# 2_waffling80_classyTKL-NMB_matrix.net
KiCad netlist of a schematic drawn in Altium Designer
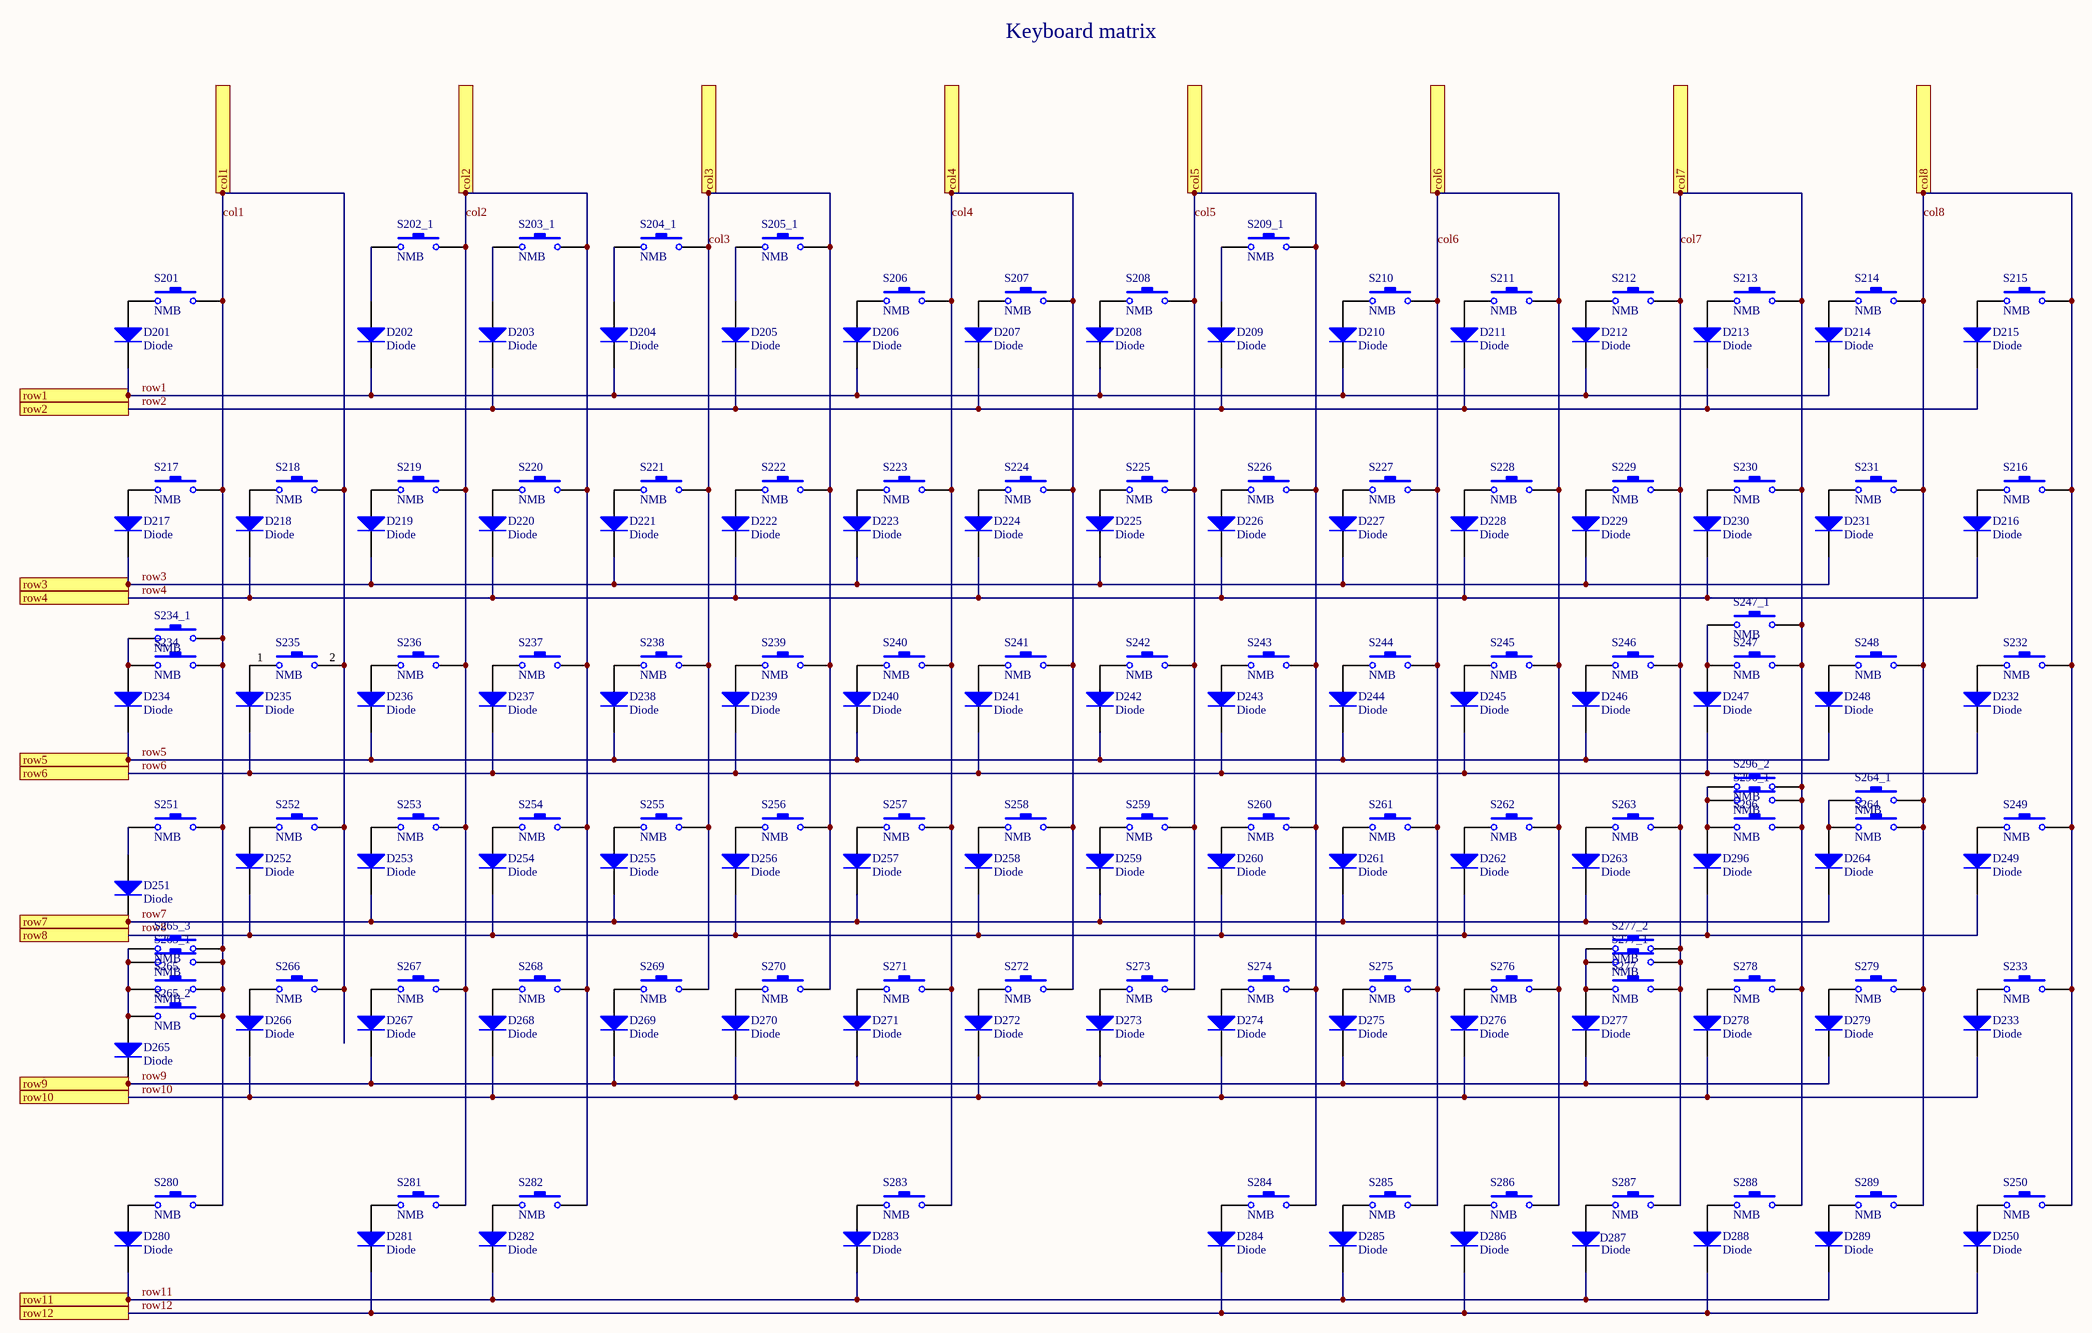
[diagram p0: 2_waffling80_classyTKL-NMB_matrix.SchDoc]

(export (version "E")
  (design (tool "Eeschema 10.0.6"))
  (components
    (comp (ref "D201")
      (value "Diode")
      (footprint "SOD-123")
      (description "Default Diode")
      (fields (field (name "LCSC PART #") "C81598") (field (name "MRF.PART") "1N4148W"))
      (libsource (lib "Miscellaneous Devices") (part "Diode"))
    )
    (comp (ref "D202")
      (value "Diode")
      (footprint "SOD-123")
      (description "Default Diode")
      (fields (field (name "LCSC PART #") "C81598") (field (name "MRF.PART") "1N4148W"))
      (libsource (lib "Miscellaneous Devices") (part "Diode"))
    )
    (comp (ref "D203")
      (value "Diode")
      (footprint "SOD-123")
      (description "Default Diode")
      (fields (field (name "LCSC PART #") "C81598") (field (name "MRF.PART") "1N4148W"))
      (libsource (lib "Miscellaneous Devices") (part "Diode"))
    )
    (comp (ref "D204")
      (value "Diode")
      (footprint "SOD-123")
      (description "Default Diode")
      (fields (field (name "LCSC PART #") "C81598") (field (name "MRF.PART") "1N4148W"))
      (libsource (lib "Miscellaneous Devices") (part "Diode"))
    )
    (comp (ref "D205")
      (value "Diode")
      (footprint "SOD-123")
      (description "Default Diode")
      (fields (field (name "LCSC PART #") "C81598") (field (name "MRF.PART") "1N4148W"))
      (libsource (lib "Miscellaneous Devices") (part "Diode"))
    )
    (comp (ref "D206")
      (value "Diode")
      (footprint "SOD-123")
      (description "Default Diode")
      (fields (field (name "LCSC PART #") "C81598") (field (name "MRF.PART") "1N4148W"))
      (libsource (lib "Miscellaneous Devices") (part "Diode"))
    )
    (comp (ref "D207")
      (value "Diode")
      (footprint "SOD-123")
      (description "Default Diode")
      (fields (field (name "LCSC PART #") "C81598") (field (name "MRF.PART") "1N4148W"))
      (libsource (lib "Miscellaneous Devices") (part "Diode"))
    )
    (comp (ref "D208")
      (value "Diode")
      (footprint "SOD-123")
      (description "Default Diode")
      (fields (field (name "LCSC PART #") "C81598") (field (name "MRF.PART") "1N4148W"))
      (libsource (lib "Miscellaneous Devices") (part "Diode"))
    )
    (comp (ref "D209")
      (value "Diode")
      (footprint "SOD-123")
      (description "Default Diode")
      (fields (field (name "LCSC PART #") "C81598") (field (name "MRF.PART") "1N4148W"))
      (libsource (lib "Miscellaneous Devices") (part "Diode"))
    )
    (comp (ref "D210")
      (value "Diode")
      (footprint "SOD-123")
      (description "Default Diode")
      (fields (field (name "LCSC PART #") "C81598") (field (name "MRF.PART") "1N4148W"))
      (libsource (lib "Miscellaneous Devices") (part "Diode"))
    )
    (comp (ref "D211")
      (value "Diode")
      (footprint "SOD-123")
      (description "Default Diode")
      (fields (field (name "LCSC PART #") "C81598") (field (name "MRF.PART") "1N4148W"))
      (libsource (lib "Miscellaneous Devices") (part "Diode"))
    )
    (comp (ref "D212")
      (value "Diode")
      (footprint "SOD-123")
      (description "Default Diode")
      (fields (field (name "LCSC PART #") "C81598") (field (name "MRF.PART") "1N4148W"))
      (libsource (lib "Miscellaneous Devices") (part "Diode"))
    )
    (comp (ref "D213")
      (value "Diode")
      (footprint "SOD-123")
      (description "Default Diode")
      (fields (field (name "LCSC PART #") "C81598") (field (name "MRF.PART") "1N4148W"))
      (libsource (lib "Miscellaneous Devices") (part "Diode"))
    )
    (comp (ref "D214")
      (value "Diode")
      (footprint "SOD-123")
      (description "Default Diode")
      (fields (field (name "LCSC PART #") "C81598") (field (name "MRF.PART") "1N4148W"))
      (libsource (lib "Miscellaneous Devices") (part "Diode"))
    )
    (comp (ref "D215")
      (value "Diode")
      (footprint "SOD-123")
      (description "Default Diode")
      (fields (field (name "LCSC PART #") "C81598") (field (name "MRF.PART") "1N4148W"))
      (libsource (lib "Miscellaneous Devices") (part "Diode"))
    )
    (comp (ref "D216")
      (value "Diode")
      (footprint "SOD-123")
      (description "Default Diode")
      (fields (field (name "LCSC PART #") "C81598") (field (name "MRF.PART") "1N4148W"))
      (libsource (lib "Miscellaneous Devices") (part "Diode"))
    )
    (comp (ref "D217")
      (value "Diode")
      (footprint "SOD-123")
      (description "Default Diode")
      (fields (field (name "LCSC PART #") "C81598") (field (name "MRF.PART") "1N4148W"))
      (libsource (lib "Miscellaneous Devices") (part "Diode"))
    )
    (comp (ref "D218")
      (value "Diode")
      (footprint "SOD-123")
      (description "Default Diode")
      (fields (field (name "LCSC PART #") "C81598") (field (name "MRF.PART") "1N4148W"))
      (libsource (lib "Miscellaneous Devices") (part "Diode"))
    )
    (comp (ref "D219")
      (value "Diode")
      (footprint "SOD-123")
      (description "Default Diode")
      (fields (field (name "LCSC PART #") "C81598") (field (name "MRF.PART") "1N4148W"))
      (libsource (lib "Miscellaneous Devices") (part "Diode"))
    )
    (comp (ref "D220")
      (value "Diode")
      (footprint "SOD-123")
      (description "Default Diode")
      (fields (field (name "LCSC PART #") "C81598") (field (name "MRF.PART") "1N4148W"))
      (libsource (lib "Miscellaneous Devices") (part "Diode"))
    )
    (comp (ref "D221")
      (value "Diode")
      (footprint "SOD-123")
      (description "Default Diode")
      (fields (field (name "LCSC PART #") "C81598") (field (name "MRF.PART") "1N4148W"))
      (libsource (lib "Miscellaneous Devices") (part "Diode"))
    )
    (comp (ref "D222")
      (value "Diode")
      (footprint "SOD-123")
      (description "Default Diode")
      (fields (field (name "LCSC PART #") "C81598") (field (name "MRF.PART") "1N4148W"))
      (libsource (lib "Miscellaneous Devices") (part "Diode"))
    )
    (comp (ref "D223")
      (value "Diode")
      (footprint "SOD-123")
      (description "Default Diode")
      (fields (field (name "LCSC PART #") "C81598") (field (name "MRF.PART") "1N4148W"))
      (libsource (lib "Miscellaneous Devices") (part "Diode"))
    )
    (comp (ref "D224")
      (value "Diode")
      (footprint "SOD-123")
      (description "Default Diode")
      (fields (field (name "LCSC PART #") "C81598") (field (name "MRF.PART") "1N4148W"))
      (libsource (lib "Miscellaneous Devices") (part "Diode"))
    )
    (comp (ref "D225")
      (value "Diode")
      (footprint "SOD-123")
      (description "Default Diode")
      (fields (field (name "LCSC PART #") "C81598") (field (name "MRF.PART") "1N4148W"))
      (libsource (lib "Miscellaneous Devices") (part "Diode"))
    )
    (comp (ref "D226")
      (value "Diode")
      (footprint "SOD-123")
      (description "Default Diode")
      (fields (field (name "LCSC PART #") "C81598") (field (name "MRF.PART") "1N4148W"))
      (libsource (lib "Miscellaneous Devices") (part "Diode"))
    )
    (comp (ref "D227")
      (value "Diode")
      (footprint "SOD-123")
      (description "Default Diode")
      (fields (field (name "LCSC PART #") "C81598") (field (name "MRF.PART") "1N4148W"))
      (libsource (lib "Miscellaneous Devices") (part "Diode"))
    )
    (comp (ref "D228")
      (value "Diode")
      (footprint "SOD-123")
      (description "Default Diode")
      (fields (field (name "LCSC PART #") "C81598") (field (name "MRF.PART") "1N4148W"))
      (libsource (lib "Miscellaneous Devices") (part "Diode"))
    )
    (comp (ref "D229")
      (value "Diode")
      (footprint "SOD-123")
      (description "Default Diode")
      (fields (field (name "LCSC PART #") "C81598") (field (name "MRF.PART") "1N4148W"))
      (libsource (lib "Miscellaneous Devices") (part "Diode"))
    )
    (comp (ref "D230")
      (value "Diode")
      (footprint "SOD-123")
      (description "Default Diode")
      (fields (field (name "LCSC PART #") "C81598") (field (name "MRF.PART") "1N4148W"))
      (libsource (lib "Miscellaneous Devices") (part "Diode"))
    )
    (comp (ref "D231")
      (value "Diode")
      (footprint "SOD-123")
      (description "Default Diode")
      (fields (field (name "LCSC PART #") "C81598") (field (name "MRF.PART") "1N4148W"))
      (libsource (lib "Miscellaneous Devices") (part "Diode"))
    )
    (comp (ref "D232")
      (value "Diode")
      (footprint "SOD-123")
      (description "Default Diode")
      (fields (field (name "LCSC PART #") "C81598") (field (name "MRF.PART") "1N4148W"))
      (libsource (lib "Miscellaneous Devices") (part "Diode"))
    )
    (comp (ref "D233")
      (value "Diode")
      (footprint "SOD-123")
      (description "Default Diode")
      (fields (field (name "LCSC PART #") "C81598") (field (name "MRF.PART") "1N4148W"))
      (libsource (lib "Miscellaneous Devices") (part "Diode"))
    )
    (comp (ref "D234")
      (value "Diode")
      (footprint "SOD-123")
      (description "Default Diode")
      (fields (field (name "LCSC PART #") "C81598") (field (name "MRF.PART") "1N4148W"))
      (libsource (lib "Miscellaneous Devices") (part "Diode"))
    )
    (comp (ref "D235")
      (value "Diode")
      (footprint "SOD-123")
      (description "Default Diode")
      (fields (field (name "LCSC PART #") "C81598") (field (name "MRF.PART") "1N4148W"))
      (libsource (lib "Miscellaneous Devices") (part "Diode"))
    )
    (comp (ref "D236")
      (value "Diode")
      (footprint "SOD-123")
      (description "Default Diode")
      (fields (field (name "LCSC PART #") "C81598") (field (name "MRF.PART") "1N4148W"))
      (libsource (lib "Miscellaneous Devices") (part "Diode"))
    )
    (comp (ref "D237")
      (value "Diode")
      (footprint "SOD-123")
      (description "Default Diode")
      (fields (field (name "LCSC PART #") "C81598") (field (name "MRF.PART") "1N4148W"))
      (libsource (lib "Miscellaneous Devices") (part "Diode"))
    )
    (comp (ref "D238")
      (value "Diode")
      (footprint "SOD-123")
      (description "Default Diode")
      (fields (field (name "LCSC PART #") "C81598") (field (name "MRF.PART") "1N4148W"))
      (libsource (lib "Miscellaneous Devices") (part "Diode"))
    )
    (comp (ref "D239")
      (value "Diode")
      (footprint "SOD-123")
      (description "Default Diode")
      (fields (field (name "LCSC PART #") "C81598") (field (name "MRF.PART") "1N4148W"))
      (libsource (lib "Miscellaneous Devices") (part "Diode"))
    )
    (comp (ref "D240")
      (value "Diode")
      (footprint "SOD-123")
      (description "Default Diode")
      (fields (field (name "LCSC PART #") "C81598") (field (name "MRF.PART") "1N4148W"))
      (libsource (lib "Miscellaneous Devices") (part "Diode"))
    )
    (comp (ref "D241")
      (value "Diode")
      (footprint "SOD-123")
      (description "Default Diode")
      (fields (field (name "LCSC PART #") "C81598") (field (name "MRF.PART") "1N4148W"))
      (libsource (lib "Miscellaneous Devices") (part "Diode"))
    )
    (comp (ref "D242")
      (value "Diode")
      (footprint "SOD-123")
      (description "Default Diode")
      (fields (field (name "LCSC PART #") "C81598") (field (name "MRF.PART") "1N4148W"))
      (libsource (lib "Miscellaneous Devices") (part "Diode"))
    )
    (comp (ref "D243")
      (value "Diode")
      (footprint "SOD-123")
      (description "Default Diode")
      (fields (field (name "LCSC PART #") "C81598") (field (name "MRF.PART") "1N4148W"))
      (libsource (lib "Miscellaneous Devices") (part "Diode"))
    )
    (comp (ref "D244")
      (value "Diode")
      (footprint "SOD-123")
      (description "Default Diode")
      (fields (field (name "LCSC PART #") "C81598") (field (name "MRF.PART") "1N4148W"))
      (libsource (lib "Miscellaneous Devices") (part "Diode"))
    )
    (comp (ref "D245")
      (value "Diode")
      (footprint "SOD-123")
      (description "Default Diode")
      (fields (field (name "LCSC PART #") "C81598") (field (name "MRF.PART") "1N4148W"))
      (libsource (lib "Miscellaneous Devices") (part "Diode"))
    )
    (comp (ref "D246")
      (value "Diode")
      (footprint "SOD-123")
      (description "Default Diode")
      (fields (field (name "LCSC PART #") "C81598") (field (name "MRF.PART") "1N4148W"))
      (libsource (lib "Miscellaneous Devices") (part "Diode"))
    )
    (comp (ref "D247")
      (value "Diode")
      (footprint "SOD-123")
      (description "Default Diode")
      (fields (field (name "LCSC PART #") "C81598") (field (name "MRF.PART") "1N4148W"))
      (libsource (lib "Miscellaneous Devices") (part "Diode"))
    )
    (comp (ref "D248")
      (value "Diode")
      (footprint "SOD-123")
      (description "Default Diode")
      (fields (field (name "LCSC PART #") "C81598") (field (name "MRF.PART") "1N4148W"))
      (libsource (lib "Miscellaneous Devices") (part "Diode"))
    )
    (comp (ref "D249")
      (value "Diode")
      (footprint "SOD-123")
      (description "Default Diode")
      (fields (field (name "LCSC PART #") "C81598") (field (name "MRF.PART") "1N4148W"))
      (libsource (lib "Miscellaneous Devices") (part "Diode"))
    )
    (comp (ref "D250")
      (value "Diode")
      (footprint "SOD-123")
      (description "Default Diode")
      (fields (field (name "LCSC PART #") "C81598") (field (name "MRF.PART") "1N4148W"))
      (libsource (lib "Miscellaneous Devices") (part "Diode"))
    )
    (comp (ref "D251")
      (value "Diode")
      (footprint "SOD-123")
      (description "Default Diode")
      (fields (field (name "LCSC PART #") "C81598") (field (name "MRF.PART") "1N4148W"))
      (libsource (lib "Miscellaneous Devices") (part "Diode"))
    )
    (comp (ref "D252")
      (value "Diode")
      (footprint "SOD-123")
      (description "Default Diode")
      (fields (field (name "LCSC PART #") "C81598") (field (name "MRF.PART") "1N4148W"))
      (libsource (lib "Miscellaneous Devices") (part "Diode"))
    )
    (comp (ref "D253")
      (value "Diode")
      (footprint "SOD-123")
      (description "Default Diode")
      (fields (field (name "LCSC PART #") "C81598") (field (name "MRF.PART") "1N4148W"))
      (libsource (lib "Miscellaneous Devices") (part "Diode"))
    )
    (comp (ref "D254")
      (value "Diode")
      (footprint "SOD-123")
      (description "Default Diode")
      (fields (field (name "LCSC PART #") "C81598") (field (name "MRF.PART") "1N4148W"))
      (libsource (lib "Miscellaneous Devices") (part "Diode"))
    )
    (comp (ref "D255")
      (value "Diode")
      (footprint "SOD-123")
      (description "Default Diode")
      (fields (field (name "LCSC PART #") "C81598") (field (name "MRF.PART") "1N4148W"))
      (libsource (lib "Miscellaneous Devices") (part "Diode"))
    )
    (comp (ref "D256")
      (value "Diode")
      (footprint "SOD-123")
      (description "Default Diode")
      (fields (field (name "LCSC PART #") "C81598") (field (name "MRF.PART") "1N4148W"))
      (libsource (lib "Miscellaneous Devices") (part "Diode"))
    )
    (comp (ref "D257")
      (value "Diode")
      (footprint "SOD-123")
      (description "Default Diode")
      (fields (field (name "LCSC PART #") "C81598") (field (name "MRF.PART") "1N4148W"))
      (libsource (lib "Miscellaneous Devices") (part "Diode"))
    )
    (comp (ref "D258")
      (value "Diode")
      (footprint "SOD-123")
      (description "Default Diode")
      (fields (field (name "LCSC PART #") "C81598") (field (name "MRF.PART") "1N4148W"))
      (libsource (lib "Miscellaneous Devices") (part "Diode"))
    )
    (comp (ref "D259")
      (value "Diode")
      (footprint "SOD-123")
      (description "Default Diode")
      (fields (field (name "LCSC PART #") "C81598") (field (name "MRF.PART") "1N4148W"))
      (libsource (lib "Miscellaneous Devices") (part "Diode"))
    )
    (comp (ref "D260")
      (value "Diode")
      (footprint "SOD-123")
      (description "Default Diode")
      (fields (field (name "LCSC PART #") "C81598") (field (name "MRF.PART") "1N4148W"))
      (libsource (lib "Miscellaneous Devices") (part "Diode"))
    )
    (comp (ref "D261")
      (value "Diode")
      (footprint "SOD-123")
      (description "Default Diode")
      (fields (field (name "LCSC PART #") "C81598") (field (name "MRF.PART") "1N4148W"))
      (libsource (lib "Miscellaneous Devices") (part "Diode"))
    )
    (comp (ref "D262")
      (value "Diode")
      (footprint "SOD-123")
      (description "Default Diode")
      (fields (field (name "LCSC PART #") "C81598") (field (name "MRF.PART") "1N4148W"))
      (libsource (lib "Miscellaneous Devices") (part "Diode"))
    )
    (comp (ref "D263")
      (value "Diode")
      (footprint "SOD-123")
      (description "Default Diode")
      (fields (field (name "LCSC PART #") "C81598") (field (name "MRF.PART") "1N4148W"))
      (libsource (lib "Miscellaneous Devices") (part "Diode"))
    )
    (comp (ref "D264")
      (value "Diode")
      (footprint "SOD-123")
      (description "Default Diode")
      (fields (field (name "LCSC PART #") "C81598") (field (name "MRF.PART") "1N4148W"))
      (libsource (lib "Miscellaneous Devices") (part "Diode"))
    )
    (comp (ref "D265")
      (value "Diode")
      (footprint "SOD-123")
      (description "Default Diode")
      (fields (field (name "LCSC PART #") "C81598") (field (name "MRF.PART") "1N4148W"))
      (libsource (lib "Miscellaneous Devices") (part "Diode"))
    )
    (comp (ref "D266")
      (value "Diode")
      (footprint "SOD-123")
      (description "Default Diode")
      (fields (field (name "LCSC PART #") "C81598") (field (name "MRF.PART") "1N4148W"))
      (libsource (lib "Miscellaneous Devices") (part "Diode"))
    )
    (comp (ref "D267")
      (value "Diode")
      (footprint "SOD-123")
      (description "Default Diode")
      (fields (field (name "LCSC PART #") "C81598") (field (name "MRF.PART") "1N4148W"))
      (libsource (lib "Miscellaneous Devices") (part "Diode"))
    )
    (comp (ref "D268")
      (value "Diode")
      (footprint "SOD-123")
      (description "Default Diode")
      (fields (field (name "LCSC PART #") "C81598") (field (name "MRF.PART") "1N4148W"))
      (libsource (lib "Miscellaneous Devices") (part "Diode"))
    )
    (comp (ref "D269")
      (value "Diode")
      (footprint "SOD-123")
      (description "Default Diode")
      (fields (field (name "LCSC PART #") "C81598") (field (name "MRF.PART") "1N4148W"))
      (libsource (lib "Miscellaneous Devices") (part "Diode"))
    )
    (comp (ref "D270")
      (value "Diode")
      (footprint "SOD-123")
      (description "Default Diode")
      (fields (field (name "LCSC PART #") "C81598") (field (name "MRF.PART") "1N4148W"))
      (libsource (lib "Miscellaneous Devices") (part "Diode"))
    )
    (comp (ref "D271")
      (value "Diode")
      (footprint "SOD-123")
      (description "Default Diode")
      (fields (field (name "LCSC PART #") "C81598") (field (name "MRF.PART") "1N4148W"))
      (libsource (lib "Miscellaneous Devices") (part "Diode"))
    )
    (comp (ref "D272")
      (value "Diode")
      (footprint "SOD-123")
      (description "Default Diode")
      (fields (field (name "LCSC PART #") "C81598") (field (name "MRF.PART") "1N4148W"))
      (libsource (lib "Miscellaneous Devices") (part "Diode"))
    )
    (comp (ref "D273")
      (value "Diode")
      (footprint "SOD-123")
      (description "Default Diode")
      (fields (field (name "LCSC PART #") "C81598") (field (name "MRF.PART") "1N4148W"))
      (libsource (lib "Miscellaneous Devices") (part "Diode"))
    )
    (comp (ref "D274")
      (value "Diode")
      (footprint "SOD-123")
      (description "Default Diode")
      (fields (field (name "LCSC PART #") "C81598") (field (name "MRF.PART") "1N4148W"))
      (libsource (lib "Miscellaneous Devices") (part "Diode"))
    )
    (comp (ref "D275")
      (value "Diode")
      (footprint "SOD-123")
      (description "Default Diode")
      (fields (field (name "LCSC PART #") "C81598") (field (name "MRF.PART") "1N4148W"))
      (libsource (lib "Miscellaneous Devices") (part "Diode"))
    )
    (comp (ref "D276")
      (value "Diode")
      (footprint "SOD-123")
      (description "Default Diode")
      (fields (field (name "LCSC PART #") "C81598") (field (name "MRF.PART") "1N4148W"))
      (libsource (lib "Miscellaneous Devices") (part "Diode"))
    )
    (comp (ref "D277")
      (value "Diode")
      (footprint "SOD-123")
      (description "Default Diode")
      (fields (field (name "LCSC PART #") "C81598") (field (name "MRF.PART") "1N4148W"))
      (libsource (lib "Miscellaneous Devices") (part "Diode"))
    )
    (comp (ref "D278")
      (value "Diode")
      (footprint "SOD-123")
      (description "Default Diode")
      (fields (field (name "LCSC PART #") "C81598") (field (name "MRF.PART") "1N4148W"))
      (libsource (lib "Miscellaneous Devices") (part "Diode"))
    )
    (comp (ref "D279")
      (value "Diode")
      (footprint "SOD-123")
      (description "Default Diode")
      (fields (field (name "LCSC PART #") "C81598") (field (name "MRF.PART") "1N4148W"))
      (libsource (lib "Miscellaneous Devices") (part "Diode"))
    )
    (comp (ref "D280")
      (value "Diode")
      (footprint "SOD-123")
      (description "Default Diode")
      (fields (field (name "LCSC PART #") "C81598") (field (name "MRF.PART") "1N4148W"))
      (libsource (lib "Miscellaneous Devices") (part "Diode"))
    )
    (comp (ref "D281")
      (value "Diode")
      (footprint "SOD-123")
      (description "Default Diode")
      (fields (field (name "LCSC PART #") "C81598") (field (name "MRF.PART") "1N4148W"))
      (libsource (lib "Miscellaneous Devices") (part "Diode"))
    )
    (comp (ref "D282")
      (value "Diode")
      (footprint "SOD-123")
      (description "Default Diode")
      (fields (field (name "LCSC PART #") "C81598") (field (name "MRF.PART") "1N4148W"))
      (libsource (lib "Miscellaneous Devices") (part "Diode"))
    )
    (comp (ref "D283")
      (value "Diode")
      (footprint "SOD-123")
      (description "Default Diode")
      (fields (field (name "LCSC PART #") "C81598") (field (name "MRF.PART") "1N4148W"))
      (libsource (lib "Miscellaneous Devices") (part "Diode"))
    )
    (comp (ref "D284")
      (value "Diode")
      (footprint "SOD-123")
      (description "Default Diode")
      (fields (field (name "LCSC PART #") "C81598") (field (name "MRF.PART") "1N4148W"))
      (libsource (lib "Miscellaneous Devices") (part "Diode"))
    )
    (comp (ref "D285")
      (value "Diode")
      (footprint "SOD-123")
      (description "Default Diode")
      (fields (field (name "LCSC PART #") "C81598") (field (name "MRF.PART") "1N4148W"))
      (libsource (lib "Miscellaneous Devices") (part "Diode"))
    )
    (comp (ref "D286")
      (value "Diode")
      (footprint "SOD-123")
      (description "Default Diode")
      (fields (field (name "LCSC PART #") "C81598") (field (name "MRF.PART") "1N4148W"))
      (libsource (lib "Miscellaneous Devices") (part "Diode"))
    )
    (comp (ref "D287")
      (value "Diode")
      (footprint "SOD-123")
      (description "Default Diode")
      (fields (field (name "LCSC PART #") "C81598") (field (name "MRF.PART") "1N4148W"))
      (libsource (lib "Miscellaneous Devices") (part "Diode"))
    )
    (comp (ref "D288")
      (value "Diode")
      (footprint "SOD-123")
      (description "Default Diode")
      (fields (field (name "LCSC PART #") "C81598") (field (name "MRF.PART") "1N4148W"))
      (libsource (lib "Miscellaneous Devices") (part "Diode"))
    )
    (comp (ref "D289")
      (value "Diode")
      (footprint "SOD-123")
      (description "Default Diode")
      (fields (field (name "LCSC PART #") "C81598") (field (name "MRF.PART") "1N4148W"))
      (libsource (lib "Miscellaneous Devices") (part "Diode"))
    )
    (comp (ref "D296")
      (value "Diode")
      (footprint "SOD-123")
      (description "Default Diode")
      (fields (field (name "LCSC PART #") "C81598") (field (name "MRF.PART") "1N4148W"))
      (libsource (lib "Miscellaneous Devices") (part "Diode"))
    )
    (comp (ref "S201")
      (value "NMB")
      (footprint "NMB-Switch 1U - switched pol  - no allignment pins")
      (description "Switch")
      (libsource (lib "Miscellaneous Devices") (part "SW-PB"))
    )
    (comp (ref "S202_1")
      (value "NMB")
      (footprint "NMB-Switch 1U - no allignment pins")
      (description "Switch")
      (libsource (lib "Miscellaneous Devices") (part "SW-PB"))
    )
    (comp (ref "S203_1")
      (value "NMB")
      (footprint "NMB-Switch 1U - no allignment pins")
      (description "Switch")
      (libsource (lib "Miscellaneous Devices") (part "SW-PB"))
    )
    (comp (ref "S204_1")
      (value "NMB")
      (footprint "NMB-Switch 1U - no allignment pins")
      (description "Switch")
      (libsource (lib "Miscellaneous Devices") (part "SW-PB"))
    )
    (comp (ref "S205_1")
      (value "NMB")
      (footprint "NMB-Switch 1U - switched pol  - no allignment pins")
      (description "Switch")
      (libsource (lib "Miscellaneous Devices") (part "SW-PB"))
    )
    (comp (ref "S206")
      (value "NMB")
      (footprint "NMB-Switch 1U - no allignment pins")
      (description "Switch")
      (libsource (lib "Miscellaneous Devices") (part "SW-PB"))
    )
    (comp (ref "S207")
      (value "NMB")
      (footprint "NMB-Switch 1U - no allignment pins")
      (description "Switch")
      (libsource (lib "Miscellaneous Devices") (part "SW-PB"))
    )
    (comp (ref "S208")
      (value "NMB")
      (footprint "NMB-Switch 1U - no allignment pins")
      (description "Switch")
      (libsource (lib "Miscellaneous Devices") (part "SW-PB"))
    )
    (comp (ref "S209_1")
      (value "NMB")
      (footprint "NMB-Switch 1U - no allignment pins")
      (description "Switch")
      (libsource (lib "Miscellaneous Devices") (part "SW-PB"))
    )
    (comp (ref "S210")
      (value "NMB")
      (footprint "NMB-Switch 1U - no allignment pins")
      (description "Switch")
      (libsource (lib "Miscellaneous Devices") (part "SW-PB"))
    )
    (comp (ref "S211")
      (value "NMB")
      (footprint "NMB-Switch 1U - no allignment pins")
      (description "Switch")
      (libsource (lib "Miscellaneous Devices") (part "SW-PB"))
    )
    (comp (ref "S212")
      (value "NMB")
      (footprint "NMB-Switch 1U - no allignment pins")
      (description "Switch")
      (libsource (lib "Miscellaneous Devices") (part "SW-PB"))
    )
    (comp (ref "S213")
      (value "NMB")
      (footprint "NMB-Switch 1U - no allignment pins")
      (description "Switch")
      (libsource (lib "Miscellaneous Devices") (part "SW-PB"))
    )
    (comp (ref "S214")
      (value "NMB")
      (footprint "NMB-Switch 1U - switched pol  - no allignment pins")
      (description "Switch")
      (libsource (lib "Miscellaneous Devices") (part "SW-PB"))
    )
    (comp (ref "S215")
      (value "NMB")
      (footprint "NMB-Switch 1U - no allignment pins")
      (description "Switch")
      (libsource (lib "Miscellaneous Devices") (part "SW-PB"))
    )
    (comp (ref "S216")
      (value "NMB")
      (footprint "NMB-Switch 1U - no allignment pins")
      (description "Switch")
      (libsource (lib "Miscellaneous Devices") (part "SW-PB"))
    )
    (comp (ref "S217")
      (value "NMB")
      (footprint "NMB-Switch 1U - switched pol  - no allignment pins")
      (description "Switch")
      (libsource (lib "Miscellaneous Devices") (part "SW-PB"))
    )
    (comp (ref "S218")
      (value "NMB")
      (footprint "NMB-Switch 1U - switched pol")
      (description "Switch")
      (libsource (lib "Miscellaneous Devices") (part "SW-PB"))
    )
    (comp (ref "S219")
      (value "NMB")
      (footprint "NMB-Switch 1U - switched pol  - no allignment pins")
      (description "Switch")
      (libsource (lib "Miscellaneous Devices") (part "SW-PB"))
    )
    (comp (ref "S220")
      (value "NMB")
      (footprint "NMB-Switch 1U - switched pol  - no allignment pins")
      (description "Switch")
      (libsource (lib "Miscellaneous Devices") (part "SW-PB"))
    )
    (comp (ref "S221")
      (value "NMB")
      (footprint "NMB-Switch 1U - switched pol  - no allignment pins")
      (description "Switch")
      (libsource (lib "Miscellaneous Devices") (part "SW-PB"))
    )
    (comp (ref "S222")
      (value "NMB")
      (footprint "NMB-Switch 1U - switched pol  - no allignment pins")
      (description "Switch")
      (libsource (lib "Miscellaneous Devices") (part "SW-PB"))
    )
    (comp (ref "S223")
      (value "NMB")
      (footprint "NMB-Switch 1U - switched pol  - no allignment pins")
      (description "Switch")
      (libsource (lib "Miscellaneous Devices") (part "SW-PB"))
    )
    (comp (ref "S224")
      (value "NMB")
      (footprint "NMB-Switch 1U - switched pol  - no allignment pins")
      (description "Switch")
      (libsource (lib "Miscellaneous Devices") (part "SW-PB"))
    )
    (comp (ref "S225")
      (value "NMB")
      (footprint "NMB-Switch 1U - switched pol  - no allignment pins")
      (description "Switch")
      (libsource (lib "Miscellaneous Devices") (part "SW-PB"))
    )
    (comp (ref "S226")
      (value "NMB")
      (footprint "NMB-Switch 1U - switched pol  - no allignment pins")
      (description "Switch")
      (libsource (lib "Miscellaneous Devices") (part "SW-PB"))
    )
    (comp (ref "S227")
      (value "NMB")
      (footprint "NMB-Switch 1U - switched pol  - no allignment pins")
      (description "Switch")
      (libsource (lib "Miscellaneous Devices") (part "SW-PB"))
    )
    (comp (ref "S228")
      (value "NMB")
      (footprint "NMB-Switch 1U - no allignment pins")
      (description "Switch")
      (libsource (lib "Miscellaneous Devices") (part "SW-PB"))
    )
    (comp (ref "S229")
      (value "NMB")
      (footprint "NMB-Switch 1U - switched pol  - no allignment pins")
      (description "Switch")
      (libsource (lib "Miscellaneous Devices") (part "SW-PB"))
    )
    (comp (ref "S230")
      (value "NMB")
      (footprint "NMB-Switch 1U - no allignment pins")
      (description "Switch")
      (libsource (lib "Miscellaneous Devices") (part "SW-PB"))
    )
    (comp (ref "S231")
      (value "NMB")
      (footprint "NMB-Switch 1U - no allignment pins")
      (description "Switch")
      (libsource (lib "Miscellaneous Devices") (part "SW-PB"))
    )
    (comp (ref "S232")
      (value "NMB")
      (footprint "NMB-Switch 1U")
      (description "Switch")
      (libsource (lib "Miscellaneous Devices") (part "SW-PB"))
    )
    (comp (ref "S233")
      (value "NMB")
      (footprint "NMB-Switch 1U - no allignment pins")
      (description "Switch")
      (libsource (lib "Miscellaneous Devices") (part "SW-PB"))
    )
    (comp (ref "S234")
      (value "NMB")
      (footprint "NMB-Switch 1U - switched pol  - no allignment pins")
      (description "TAB")
      (libsource (lib "Miscellaneous Devices") (part "SW-PB"))
    )
    (comp (ref "S234_1")
      (value "NMB")
      (footprint "NMB-Switch 1U - switched pol  - no allignment pins")
      (description "TAB")
      (libsource (lib "Miscellaneous Devices") (part "SW-PB"))
    )
    (comp (ref "S235")
      (value "NMB")
      (footprint "NMB-Switch 1U - switched pol  - no allignment pins")
      (description "Switch")
      (libsource (lib "") (part "SW-PB_1"))
    )
    (comp (ref "S236")
      (value "NMB")
      (footprint "NMB-Switch 1U - switched pol  - no allignment pins")
      (description "Switch")
      (libsource (lib "Miscellaneous Devices") (part "SW-PB"))
    )
    (comp (ref "S237")
      (value "NMB")
      (footprint "NMB-Switch 1U - switched pol  - no allignment pins")
      (description "Switch")
      (libsource (lib "Miscellaneous Devices") (part "SW-PB"))
    )
    (comp (ref "S238")
      (value "NMB")
      (footprint "NMB-Switch 1U - switched pol  - no allignment pins")
      (description "Switch")
      (libsource (lib "Miscellaneous Devices") (part "SW-PB"))
    )
    (comp (ref "S239")
      (value "NMB")
      (footprint "NMB-Switch 1U - switched pol  - no allignment pins")
      (description "Switch")
      (libsource (lib "Miscellaneous Devices") (part "SW-PB"))
    )
    (comp (ref "S240")
      (value "NMB")
      (footprint "NMB-Switch 1U - switched pol  - no allignment pins")
      (description "Switch")
      (libsource (lib "Miscellaneous Devices") (part "SW-PB"))
    )
    (comp (ref "S241")
      (value "NMB")
      (footprint "NMB-Switch 1U - switched pol  - no allignment pins")
      (description "Switch")
      (libsource (lib "Miscellaneous Devices") (part "SW-PB"))
    )
    (comp (ref "S242")
      (value "NMB")
      (footprint "NMB-Switch 1U - switched pol  - no allignment pins")
      (description "Switch")
      (libsource (lib "Miscellaneous Devices") (part "SW-PB"))
    )
    (comp (ref "S243")
      (value "NMB")
      (footprint "NMB-Switch 1U - switched pol  - no allignment pins")
      (description "Switch")
      (libsource (lib "Miscellaneous Devices") (part "SW-PB"))
    )
    (comp (ref "S244")
      (value "NMB")
      (footprint "NMB-Switch 1U - switched pol  - no allignment pins")
      (description "Switch")
      (libsource (lib "Miscellaneous Devices") (part "SW-PB"))
    )
    (comp (ref "S245")
      (value "NMB")
      (footprint "NMB-Switch 1U - switched pol  - no allignment pins")
      (description "Switch")
      (libsource (lib "Miscellaneous Devices") (part "SW-PB"))
    )
    (comp (ref "S246")
      (value "NMB")
      (footprint "NMB-Switch 1U - switched pol  - no allignment pins")
      (description "Switch")
      (libsource (lib "Miscellaneous Devices") (part "SW-PB"))
    )
    (comp (ref "S247")
      (value "NMB")
      (footprint "NMB-Switch 1U - no allignment pins")
      (description "Switch")
      (libsource (lib "Miscellaneous Devices") (part "SW-PB"))
    )
    (comp (ref "S247_1")
      (value "NMB")
      (footprint "NMB-Switch 1U - no allignment pins")
      (description "Switch")
      (libsource (lib "Miscellaneous Devices") (part "SW-PB"))
    )
    (comp (ref "S248")
      (value "NMB")
      (footprint "NMB-Switch 1U - no allignment pins")
      (description "Switch")
      (libsource (lib "Miscellaneous Devices") (part "SW-PB"))
    )
    (comp (ref "S249")
      (value "NMB")
      (footprint "NMB-Switch 1U - no allignment pins")
      (description "Switch")
      (libsource (lib "Miscellaneous Devices") (part "SW-PB"))
    )
    (comp (ref "S250")
      (value "NMB")
      (footprint "NMB-Switch 1U - no allignment pins")
      (description "Switch")
      (libsource (lib "Miscellaneous Devices") (part "SW-PB"))
    )
    (comp (ref "S251")
      (value "NMB")
      (footprint "NMB-Switch 1U - switched pol  - no allignment pins")
      (description "Switch")
      (libsource (lib "Miscellaneous Devices") (part "SW-PB"))
    )
    (comp (ref "S252")
      (value "NMB")
      (footprint "NMB-Switch 1U - switched pol  - no allignment pins")
      (description "Switch")
      (libsource (lib "Miscellaneous Devices") (part "SW-PB"))
    )
    (comp (ref "S253")
      (value "NMB")
      (footprint "NMB-Switch 1U - switched pol  - no allignment pins")
      (description "Switch")
      (libsource (lib "Miscellaneous Devices") (part "SW-PB"))
    )
    (comp (ref "S254")
      (value "NMB")
      (footprint "NMB-Switch 1U - switched pol  - no allignment pins")
      (description "Switch")
      (libsource (lib "Miscellaneous Devices") (part "SW-PB"))
    )
    (comp (ref "S255")
      (value "NMB")
      (footprint "NMB-Switch 1U - switched pol  - no allignment pins")
      (description "Switch")
      (libsource (lib "Miscellaneous Devices") (part "SW-PB"))
    )
    (comp (ref "S256")
      (value "NMB")
      (footprint "NMB-Switch 1U - switched pol  - no allignment pins")
      (description "Switch")
      (libsource (lib "Miscellaneous Devices") (part "SW-PB"))
    )
    (comp (ref "S257")
      (value "NMB")
      (footprint "NMB-Switch 1U - switched pol  - no allignment pins")
      (description "Switch")
      (libsource (lib "Miscellaneous Devices") (part "SW-PB"))
    )
    (comp (ref "S258")
      (value "NMB")
      (footprint "NMB-Switch 1U - switched pol")
      (description "Switch")
      (libsource (lib "Miscellaneous Devices") (part "SW-PB"))
    )
    (comp (ref "S259")
      (value "NMB")
      (footprint "NMB-Switch 1U - switched pol  - no allignment pins")
      (description "Switch")
      (libsource (lib "Miscellaneous Devices") (part "SW-PB"))
    )
    (comp (ref "S260")
      (value "NMB")
      (footprint "NMB-Switch 1U - switched pol  - no allignment pins")
      (description "Switch")
      (libsource (lib "Miscellaneous Devices") (part "SW-PB"))
    )
    (comp (ref "S261")
      (value "NMB")
      (footprint "NMB-Switch 1U - switched pol  - no allignment pins")
      (description "Switch")
      (libsource (lib "Miscellaneous Devices") (part "SW-PB"))
    )
    (comp (ref "S262")
      (value "NMB")
      (footprint "NMB-Switch 1U - switched pol  - no allignment pins")
      (description "Switch")
      (libsource (lib "Miscellaneous Devices") (part "SW-PB"))
    )
    (comp (ref "S263")
      (value "NMB")
      (footprint "NMB-Switch 1U - no allignment pins")
      (description "Switch")
      (libsource (lib "Miscellaneous Devices") (part "SW-PB"))
    )
    (comp (ref "S264")
      (value "NMB")
      (footprint "NMB-Switch 1U - no allignment pins")
      (description "Switch")
      (libsource (lib "Miscellaneous Devices") (part "SW-PB"))
    )
    (comp (ref "S264_1")
      (value "NMB")
      (footprint "NMB-Switch 1U - switched pol  - no allignment pins")
      (description "Switch")
      (libsource (lib "Miscellaneous Devices") (part "SW-PB"))
    )
    (comp (ref "S265")
      (value "NMB")
      (footprint "NMB-Switch 1U - no allignment pins")
      (description "Switch")
      (libsource (lib "Miscellaneous Devices") (part "SW-PB"))
    )
    (comp (ref "S265_1")
      (value "NMB")
      (footprint "NMB-Switch 1U - switched pol  - no allignment pins")
      (description "Switch")
      (libsource (lib "Miscellaneous Devices") (part "SW-PB"))
    )
    (comp (ref "S265_2")
      (value "NMB")
      (footprint "NMB-Switch 1U - no allignment pins")
      (description "Switch")
      (libsource (lib "Miscellaneous Devices") (part "SW-PB"))
    )
    (comp (ref "S265_3")
      (value "NMB")
      (footprint "NMB-Switch 1U - switched pol  - no allignment pins")
      (description "Switch")
      (libsource (lib "Miscellaneous Devices") (part "SW-PB"))
    )
    (comp (ref "S266")
      (value "NMB")
      (footprint "NMB-Switch 1U - switched pol")
      (description "Switch")
      (libsource (lib "Miscellaneous Devices") (part "SW-PB"))
    )
    (comp (ref "S267")
      (value "NMB")
      (footprint "NMB-Switch 1U - switched pol  - no allignment pins")
      (description "Switch")
      (libsource (lib "Miscellaneous Devices") (part "SW-PB"))
    )
    (comp (ref "S268")
      (value "NMB")
      (footprint "NMB-Switch 1U - switched pol  - no allignment pins")
      (description "Switch")
      (libsource (lib "Miscellaneous Devices") (part "SW-PB"))
    )
    (comp (ref "S269")
      (value "NMB")
      (footprint "NMB-Switch 1U - switched pol  - no allignment pins")
      (description "Switch")
      (libsource (lib "Miscellaneous Devices") (part "SW-PB"))
    )
    (comp (ref "S270")
      (value "NMB")
      (footprint "NMB-Switch 1U - switched pol  - no allignment pins")
      (description "Switch")
      (libsource (lib "Miscellaneous Devices") (part "SW-PB"))
    )
    (comp (ref "S271")
      (value "NMB")
      (footprint "NMB-Switch 1U - switched pol  - no allignment pins")
      (description "Switch")
      (libsource (lib "Miscellaneous Devices") (part "SW-PB"))
    )
    (comp (ref "S272")
      (value "NMB")
      (footprint "NMB-Switch 1U - switched pol  - no allignment pins")
      (description "Switch")
      (libsource (lib "Miscellaneous Devices") (part "SW-PB"))
    )
    (comp (ref "S273")
      (value "NMB")
      (footprint "NMB-Switch 1U - switched pol  - no allignment pins")
      (description "Switch")
      (libsource (lib "Miscellaneous Devices") (part "SW-PB"))
    )
    (comp (ref "S274")
      (value "NMB")
      (footprint "NMB-Switch 1U - switched pol  - no allignment pins")
      (description "Switch")
      (libsource (lib "Miscellaneous Devices") (part "SW-PB"))
    )
    (comp (ref "S275")
      (value "NMB")
      (footprint "NMB-Switch 1U - switched pol  - no allignment pins")
      (description "Switch")
      (libsource (lib "Miscellaneous Devices") (part "SW-PB"))
    )
    (comp (ref "S276")
      (value "NMB")
      (footprint "NMB-Switch 1U - switched pol  - no allignment pins")
      (description "Switch")
      (libsource (lib "Miscellaneous Devices") (part "SW-PB"))
    )
    (comp (ref "S277")
      (value "NMB")
      (footprint "NMB-Switch 1U - switched pol  - no allignment pins")
      (description "Switch")
      (libsource (lib "Miscellaneous Devices") (part "SW-PB"))
    )
    (comp (ref "S277_1")
      (value "NMB")
      (footprint "NMB-Switch 1U - no allignment pins")
      (description "Switch")
      (libsource (lib "Miscellaneous Devices") (part "SW-PB"))
    )
    (comp (ref "S277_2")
      (value "NMB")
      (footprint "NMB-Switch 1U - switched pol  - no allignment pins")
      (description "Switch")
      (libsource (lib "Miscellaneous Devices") (part "SW-PB"))
    )
    (comp (ref "S278")
      (value "NMB")
      (footprint "NMB-Switch 1U - switched pol  - no allignment pins")
      (description "Switch")
      (libsource (lib "Miscellaneous Devices") (part "SW-PB"))
    )
    (comp (ref "S279")
      (value "NMB")
      (footprint "NMB-Switch 1U")
      (description "Switch")
      (libsource (lib "Miscellaneous Devices") (part "SW-PB"))
    )
    (comp (ref "S280")
      (value "NMB")
      (footprint "NMB-Switch 1U - no allignment pins")
      (description "Switch")
      (libsource (lib "Miscellaneous Devices") (part "SW-PB"))
    )
    (comp (ref "S281")
      (value "NMB")
      (footprint "NMB-Switch 1U - no allignment pins")
      (description "Switch")
      (libsource (lib "Miscellaneous Devices") (part "SW-PB"))
    )
    (comp (ref "S282")
      (value "NMB")
      (footprint "NMB-Switch 1U - no allignment pins")
      (description "Switch")
      (libsource (lib "Miscellaneous Devices") (part "SW-PB"))
    )
    (comp (ref "S283")
      (value "NMB")
      (footprint "NMB-Switch 1U - no allignment pins")
      (description "Switch")
      (libsource (lib "Miscellaneous Devices") (part "SW-PB"))
    )
    (comp (ref "S284")
      (value "NMB")
      (footprint "NMB-Switch 1U - no allignment pins")
      (description "Switch")
      (libsource (lib "Miscellaneous Devices") (part "SW-PB"))
    )
    (comp (ref "S285")
      (value "NMB")
      (footprint "NMB-Switch 1U - no allignment pins")
      (description "Switch")
      (libsource (lib "Miscellaneous Devices") (part "SW-PB"))
    )
    (comp (ref "S286")
      (value "NMB")
      (footprint "NMB-Switch 1U - no allignment pins")
      (description "Switch")
      (libsource (lib "Miscellaneous Devices") (part "SW-PB"))
    )
    (comp (ref "S287")
      (value "NMB")
      (footprint "NMB-Switch 1U - no allignment pins")
      (description "Switch")
      (libsource (lib "Miscellaneous Devices") (part "SW-PB"))
    )
    (comp (ref "S288")
      (value "NMB")
      (footprint "NMB-Switch 1U - no allignment pins")
      (description "Switch")
      (libsource (lib "Miscellaneous Devices") (part "SW-PB"))
    )
    (comp (ref "S289")
      (value "NMB")
      (footprint "NMB-Switch 1U - no allignment pins")
      (description "Switch")
      (libsource (lib "Miscellaneous Devices") (part "SW-PB"))
    )
    (comp (ref "S296")
      (value "NMB")
      (footprint "NMB-Switch 1U - switched pol  - no allignment pins")
      (description "Switch")
      (libsource (lib "Miscellaneous Devices") (part "SW-PB"))
    )
    (comp (ref "S296_1")
      (value "NMB")
      (footprint "NMB-Switch 1U - no allignment pins")
      (description "Switch")
      (libsource (lib "Miscellaneous Devices") (part "SW-PB"))
    )
    (comp (ref "S296_2")
      (value "NMB")
      (footprint "NMB-Switch 1U - switched pol  - no allignment pins")
      (description "Switch")
      (libsource (lib "Miscellaneous Devices") (part "SW-PB"))
    )
  )
  (nets
    (net (code "1") (name "/col1") (class "Default")
      (node (ref "S201") (pin "2") (pinfunction "2_2") (pintype "passive"))
      (node (ref "S217") (pin "2") (pinfunction "2_2") (pintype "passive"))
      (node (ref "S218") (pin "2") (pinfunction "2_2") (pintype "passive"))
      (node (ref "S234") (pin "2") (pinfunction "2_2") (pintype "passive"))
      (node (ref "S234_1") (pin "2") (pinfunction "2_2") (pintype "passive"))
      (node (ref "S235") (pin "2") (pinfunction "2_2") (pintype "passive"))
      (node (ref "S251") (pin "2") (pinfunction "2_2") (pintype "passive"))
      (node (ref "S252") (pin "2") (pinfunction "2_2") (pintype "passive"))
      (node (ref "S265") (pin "2") (pinfunction "2_2") (pintype "passive"))
      (node (ref "S265_1") (pin "2") (pinfunction "2_2") (pintype "passive"))
      (node (ref "S265_2") (pin "2") (pinfunction "2_2") (pintype "passive"))
      (node (ref "S265_3") (pin "2") (pinfunction "2_2") (pintype "passive"))
      (node (ref "S266") (pin "2") (pinfunction "2_2") (pintype "passive"))
      (node (ref "S280") (pin "1") (pinfunction "1_1") (pintype "passive"))
    )
    (net (code "2") (name "/col2") (class "Default")
      (node (ref "S202_1") (pin "2") (pinfunction "2_2") (pintype "passive"))
      (node (ref "S203_1") (pin "2") (pinfunction "2_2") (pintype "passive"))
      (node (ref "S219") (pin "2") (pinfunction "2_2") (pintype "passive"))
      (node (ref "S220") (pin "2") (pinfunction "2_2") (pintype "passive"))
      (node (ref "S236") (pin "2") (pinfunction "2_2") (pintype "passive"))
      (node (ref "S237") (pin "2") (pinfunction "2_2") (pintype "passive"))
      (node (ref "S253") (pin "2") (pinfunction "2_2") (pintype "passive"))
      (node (ref "S254") (pin "2") (pinfunction "2_2") (pintype "passive"))
      (node (ref "S267") (pin "2") (pinfunction "2_2") (pintype "passive"))
      (node (ref "S268") (pin "2") (pinfunction "2_2") (pintype "passive"))
      (node (ref "S281") (pin "1") (pinfunction "1_1") (pintype "passive"))
      (node (ref "S282") (pin "1") (pinfunction "1_1") (pintype "passive"))
    )
    (net (code "3") (name "/col3") (class "Default")
      (node (ref "S204_1") (pin "2") (pinfunction "2_2") (pintype "passive"))
      (node (ref "S205_1") (pin "2") (pinfunction "2_2") (pintype "passive"))
      (node (ref "S221") (pin "2") (pinfunction "2_2") (pintype "passive"))
      (node (ref "S222") (pin "2") (pinfunction "2_2") (pintype "passive"))
      (node (ref "S238") (pin "2") (pinfunction "2_2") (pintype "passive"))
      (node (ref "S239") (pin "2") (pinfunction "2_2") (pintype "passive"))
      (node (ref "S255") (pin "2") (pinfunction "2_2") (pintype "passive"))
      (node (ref "S256") (pin "2") (pinfunction "2_2") (pintype "passive"))
      (node (ref "S269") (pin "2") (pinfunction "2_2") (pintype "passive"))
      (node (ref "S270") (pin "2") (pinfunction "2_2") (pintype "passive"))
    )
    (net (code "4") (name "/col4") (class "Default")
      (node (ref "S206") (pin "2") (pinfunction "2_2") (pintype "passive"))
      (node (ref "S207") (pin "2") (pinfunction "2_2") (pintype "passive"))
      (node (ref "S223") (pin "2") (pinfunction "2_2") (pintype "passive"))
      (node (ref "S224") (pin "2") (pinfunction "2_2") (pintype "passive"))
      (node (ref "S240") (pin "2") (pinfunction "2_2") (pintype "passive"))
      (node (ref "S241") (pin "2") (pinfunction "2_2") (pintype "passive"))
      (node (ref "S257") (pin "2") (pinfunction "2_2") (pintype "passive"))
      (node (ref "S258") (pin "2") (pinfunction "2_2") (pintype "passive"))
      (node (ref "S271") (pin "2") (pinfunction "2_2") (pintype "passive"))
      (node (ref "S272") (pin "2") (pinfunction "2_2") (pintype "passive"))
      (node (ref "S283") (pin "2") (pinfunction "2_2") (pintype "passive"))
    )
    (net (code "5") (name "/col5") (class "Default")
      (node (ref "S208") (pin "2") (pinfunction "2_2") (pintype "passive"))
      (node (ref "S209_1") (pin "2") (pinfunction "2_2") (pintype "passive"))
      (node (ref "S225") (pin "2") (pinfunction "2_2") (pintype "passive"))
      (node (ref "S226") (pin "2") (pinfunction "2_2") (pintype "passive"))
      (node (ref "S242") (pin "2") (pinfunction "2_2") (pintype "passive"))
      (node (ref "S243") (pin "2") (pinfunction "2_2") (pintype "passive"))
      (node (ref "S259") (pin "2") (pinfunction "2_2") (pintype "passive"))
      (node (ref "S260") (pin "2") (pinfunction "2_2") (pintype "passive"))
      (node (ref "S273") (pin "2") (pinfunction "2_2") (pintype "passive"))
      (node (ref "S274") (pin "2") (pinfunction "2_2") (pintype "passive"))
      (node (ref "S284") (pin "2") (pinfunction "2_2") (pintype "passive"))
    )
    (net (code "6") (name "/col6") (class "Default")
      (node (ref "S210") (pin "2") (pinfunction "2_2") (pintype "passive"))
      (node (ref "S211") (pin "2") (pinfunction "2_2") (pintype "passive"))
      (node (ref "S227") (pin "2") (pinfunction "2_2") (pintype "passive"))
      (node (ref "S228") (pin "2") (pinfunction "2_2") (pintype "passive"))
      (node (ref "S244") (pin "2") (pinfunction "2_2") (pintype "passive"))
      (node (ref "S245") (pin "2") (pinfunction "2_2") (pintype "passive"))
      (node (ref "S261") (pin "2") (pinfunction "2_2") (pintype "passive"))
      (node (ref "S262") (pin "2") (pinfunction "2_2") (pintype "passive"))
      (node (ref "S275") (pin "2") (pinfunction "2_2") (pintype "passive"))
      (node (ref "S276") (pin "2") (pinfunction "2_2") (pintype "passive"))
      (node (ref "S285") (pin "2") (pinfunction "2_2") (pintype "passive"))
      (node (ref "S286") (pin "2") (pinfunction "2_2") (pintype "passive"))
    )
    (net (code "7") (name "/col7") (class "Default")
      (node (ref "S212") (pin "2") (pinfunction "2_2") (pintype "passive"))
      (node (ref "S213") (pin "2") (pinfunction "2_2") (pintype "passive"))
      (node (ref "S229") (pin "2") (pinfunction "2_2") (pintype "passive"))
      (node (ref "S230") (pin "2") (pinfunction "2_2") (pintype "passive"))
      (node (ref "S246") (pin "2") (pinfunction "2_2") (pintype "passive"))
      (node (ref "S247") (pin "2") (pinfunction "2_2") (pintype "passive"))
      (node (ref "S247_1") (pin "2") (pinfunction "2_2") (pintype "passive"))
      (node (ref "S263") (pin "2") (pinfunction "2_2") (pintype "passive"))
      (node (ref "S277") (pin "2") (pinfunction "2_2") (pintype "passive"))
      (node (ref "S277_1") (pin "2") (pinfunction "2_2") (pintype "passive"))
      (node (ref "S277_2") (pin "2") (pinfunction "2_2") (pintype "passive"))
      (node (ref "S278") (pin "2") (pinfunction "2_2") (pintype "passive"))
      (node (ref "S287") (pin "2") (pinfunction "2_2") (pintype "passive"))
      (node (ref "S288") (pin "2") (pinfunction "2_2") (pintype "passive"))
      (node (ref "S296") (pin "2") (pinfunction "2_2") (pintype "passive"))
      (node (ref "S296_1") (pin "2") (pinfunction "2_2") (pintype "passive"))
      (node (ref "S296_2") (pin "2") (pinfunction "2_2") (pintype "passive"))
    )
    (net (code "8") (name "/col8") (class "Default")
      (node (ref "S214") (pin "2") (pinfunction "2_2") (pintype "passive"))
      (node (ref "S215") (pin "2") (pinfunction "2_2") (pintype "passive"))
      (node (ref "S216") (pin "2") (pinfunction "2_2") (pintype "passive"))
      (node (ref "S231") (pin "2") (pinfunction "2_2") (pintype "passive"))
      (node (ref "S232") (pin "2") (pinfunction "2_2") (pintype "passive"))
      (node (ref "S233") (pin "2") (pinfunction "2_2") (pintype "passive"))
      (node (ref "S248") (pin "2") (pinfunction "2_2") (pintype "passive"))
      (node (ref "S249") (pin "2") (pinfunction "2_2") (pintype "passive"))
      (node (ref "S250") (pin "2") (pinfunction "2_2") (pintype "passive"))
      (node (ref "S264") (pin "2") (pinfunction "2_2") (pintype "passive"))
      (node (ref "S264_1") (pin "2") (pinfunction "2_2") (pintype "passive"))
      (node (ref "S279") (pin "2") (pinfunction "2_2") (pintype "passive"))
      (node (ref "S289") (pin "2") (pinfunction "2_2") (pintype "passive"))
    )
    (net (code "9") (name "/row1") (class "Default")
      (node (ref "D201") (pin "2") (pinfunction "K_2") (pintype "passive"))
      (node (ref "D202") (pin "2") (pinfunction "K_2") (pintype "passive"))
      (node (ref "D204") (pin "2") (pinfunction "K_2") (pintype "passive"))
      (node (ref "D206") (pin "2") (pinfunction "K_2") (pintype "passive"))
      (node (ref "D208") (pin "2") (pinfunction "K_2") (pintype "passive"))
      (node (ref "D210") (pin "2") (pinfunction "K_2") (pintype "passive"))
      (node (ref "D212") (pin "2") (pinfunction "K_2") (pintype "passive"))
      (node (ref "D214") (pin "2") (pinfunction "K_2") (pintype "passive"))
    )
    (net (code "10") (name "/row2") (class "Default")
      (node (ref "D203") (pin "2") (pinfunction "K_2") (pintype "passive"))
      (node (ref "D205") (pin "2") (pinfunction "K_2") (pintype "passive"))
      (node (ref "D207") (pin "2") (pinfunction "K_2") (pintype "passive"))
      (node (ref "D209") (pin "2") (pinfunction "K_2") (pintype "passive"))
      (node (ref "D211") (pin "2") (pinfunction "K_2") (pintype "passive"))
      (node (ref "D213") (pin "2") (pinfunction "K_2") (pintype "passive"))
      (node (ref "D215") (pin "2") (pinfunction "K_2") (pintype "passive"))
    )
    (net (code "11") (name "/row3") (class "Default")
      (node (ref "D217") (pin "2") (pinfunction "K_2") (pintype "passive"))
      (node (ref "D219") (pin "2") (pinfunction "K_2") (pintype "passive"))
      (node (ref "D221") (pin "2") (pinfunction "K_2") (pintype "passive"))
      (node (ref "D223") (pin "2") (pinfunction "K_2") (pintype "passive"))
      (node (ref "D225") (pin "2") (pinfunction "K_2") (pintype "passive"))
      (node (ref "D227") (pin "2") (pinfunction "K_2") (pintype "passive"))
      (node (ref "D229") (pin "2") (pinfunction "K_2") (pintype "passive"))
      (node (ref "D231") (pin "2") (pinfunction "K_2") (pintype "passive"))
    )
    (net (code "12") (name "/row4") (class "Default")
      (node (ref "D216") (pin "2") (pinfunction "K_2") (pintype "passive"))
      (node (ref "D218") (pin "2") (pinfunction "K_2") (pintype "passive"))
      (node (ref "D220") (pin "2") (pinfunction "K_2") (pintype "passive"))
      (node (ref "D222") (pin "2") (pinfunction "K_2") (pintype "passive"))
      (node (ref "D224") (pin "2") (pinfunction "K_2") (pintype "passive"))
      (node (ref "D226") (pin "2") (pinfunction "K_2") (pintype "passive"))
      (node (ref "D228") (pin "2") (pinfunction "K_2") (pintype "passive"))
      (node (ref "D230") (pin "2") (pinfunction "K_2") (pintype "passive"))
    )
    (net (code "13") (name "/row5") (class "Default")
      (node (ref "D234") (pin "2") (pinfunction "K_2") (pintype "passive"))
      (node (ref "D236") (pin "2") (pinfunction "K_2") (pintype "passive"))
      (node (ref "D238") (pin "2") (pinfunction "K_2") (pintype "passive"))
      (node (ref "D240") (pin "2") (pinfunction "K_2") (pintype "passive"))
      (node (ref "D242") (pin "2") (pinfunction "K_2") (pintype "passive"))
      (node (ref "D244") (pin "2") (pinfunction "K_2") (pintype "passive"))
      (node (ref "D246") (pin "2") (pinfunction "K_2") (pintype "passive"))
      (node (ref "D248") (pin "2") (pinfunction "K_2") (pintype "passive"))
    )
    (net (code "14") (name "/row6") (class "Default")
      (node (ref "D232") (pin "2") (pinfunction "K_2") (pintype "passive"))
      (node (ref "D235") (pin "2") (pinfunction "K_2") (pintype "passive"))
      (node (ref "D237") (pin "2") (pinfunction "K_2") (pintype "passive"))
      (node (ref "D239") (pin "2") (pinfunction "K_2") (pintype "passive"))
      (node (ref "D241") (pin "2") (pinfunction "K_2") (pintype "passive"))
      (node (ref "D243") (pin "2") (pinfunction "K_2") (pintype "passive"))
      (node (ref "D245") (pin "2") (pinfunction "K_2") (pintype "passive"))
      (node (ref "D247") (pin "2") (pinfunction "K_2") (pintype "passive"))
    )
    (net (code "15") (name "/row7") (class "Default")
      (node (ref "D251") (pin "2") (pinfunction "K_2") (pintype "passive"))
      (node (ref "D253") (pin "2") (pinfunction "K_2") (pintype "passive"))
      (node (ref "D255") (pin "2") (pinfunction "K_2") (pintype "passive"))
      (node (ref "D257") (pin "2") (pinfunction "K_2") (pintype "passive"))
      (node (ref "D259") (pin "2") (pinfunction "K_2") (pintype "passive"))
      (node (ref "D261") (pin "2") (pinfunction "K_2") (pintype "passive"))
      (node (ref "D263") (pin "2") (pinfunction "K_2") (pintype "passive"))
      (node (ref "D264") (pin "2") (pinfunction "K_2") (pintype "passive"))
    )
    (net (code "16") (name "/row8") (class "Default")
      (node (ref "D249") (pin "2") (pinfunction "K_2") (pintype "passive"))
      (node (ref "D252") (pin "2") (pinfunction "K_2") (pintype "passive"))
      (node (ref "D254") (pin "2") (pinfunction "K_2") (pintype "passive"))
      (node (ref "D256") (pin "2") (pinfunction "K_2") (pintype "passive"))
      (node (ref "D258") (pin "2") (pinfunction "K_2") (pintype "passive"))
      (node (ref "D260") (pin "2") (pinfunction "K_2") (pintype "passive"))
      (node (ref "D262") (pin "2") (pinfunction "K_2") (pintype "passive"))
      (node (ref "D296") (pin "2") (pinfunction "K_2") (pintype "passive"))
    )
    (net (code "17") (name "/row9") (class "Default")
      (node (ref "D265") (pin "2") (pinfunction "K_2") (pintype "passive"))
      (node (ref "D267") (pin "2") (pinfunction "K_2") (pintype "passive"))
      (node (ref "D269") (pin "2") (pinfunction "K_2") (pintype "passive"))
      (node (ref "D271") (pin "2") (pinfunction "K_2") (pintype "passive"))
      (node (ref "D273") (pin "2") (pinfunction "K_2") (pintype "passive"))
      (node (ref "D275") (pin "2") (pinfunction "K_2") (pintype "passive"))
      (node (ref "D277") (pin "2") (pinfunction "K_2") (pintype "passive"))
      (node (ref "D279") (pin "2") (pinfunction "K_2") (pintype "passive"))
    )
    (net (code "18") (name "/row10") (class "Default")
      (node (ref "D233") (pin "2") (pinfunction "K_2") (pintype "passive"))
      (node (ref "D266") (pin "2") (pinfunction "K_2") (pintype "passive"))
      (node (ref "D268") (pin "2") (pinfunction "K_2") (pintype "passive"))
      (node (ref "D270") (pin "2") (pinfunction "K_2") (pintype "passive"))
      (node (ref "D272") (pin "2") (pinfunction "K_2") (pintype "passive"))
      (node (ref "D274") (pin "2") (pinfunction "K_2") (pintype "passive"))
      (node (ref "D276") (pin "2") (pinfunction "K_2") (pintype "passive"))
      (node (ref "D278") (pin "2") (pinfunction "K_2") (pintype "passive"))
    )
    (net (code "19") (name "/row11") (class "Default")
      (node (ref "D280") (pin "2") (pinfunction "K_2") (pintype "passive"))
      (node (ref "D282") (pin "2") (pinfunction "K_2") (pintype "passive"))
      (node (ref "D283") (pin "2") (pinfunction "K_2") (pintype "passive"))
      (node (ref "D285") (pin "2") (pinfunction "K_2") (pintype "passive"))
      (node (ref "D287") (pin "2") (pinfunction "K_2") (pintype "passive"))
      (node (ref "D289") (pin "2") (pinfunction "K_2") (pintype "passive"))
    )
    (net (code "20") (name "/row12") (class "Default")
      (node (ref "D250") (pin "2") (pinfunction "K_2") (pintype "passive"))
      (node (ref "D281") (pin "2") (pinfunction "K_2") (pintype "passive"))
      (node (ref "D284") (pin "2") (pinfunction "K_2") (pintype "passive"))
      (node (ref "D286") (pin "2") (pinfunction "K_2") (pintype "passive"))
      (node (ref "D288") (pin "2") (pinfunction "K_2") (pintype "passive"))
    )
    (net (code "21") (name "Net-(D201-A)") (class "Default")
      (node (ref "D201") (pin "1") (pinfunction "A_1") (pintype "passive"))
      (node (ref "S201") (pin "1") (pinfunction "1_1") (pintype "passive"))
    )
    (net (code "22") (name "Net-(D202-A)") (class "Default")
      (node (ref "D202") (pin "1") (pinfunction "A_1") (pintype "passive"))
      (node (ref "S202_1") (pin "1") (pinfunction "1_1") (pintype "passive"))
    )
    (net (code "23") (name "Net-(D203-A)") (class "Default")
      (node (ref "D203") (pin "1") (pinfunction "A_1") (pintype "passive"))
      (node (ref "S203_1") (pin "1") (pinfunction "1_1") (pintype "passive"))
    )
    (net (code "24") (name "Net-(D204-A)") (class "Default")
      (node (ref "D204") (pin "1") (pinfunction "A_1") (pintype "passive"))
      (node (ref "S204_1") (pin "1") (pinfunction "1_1") (pintype "passive"))
    )
    (net (code "25") (name "Net-(D205-A)") (class "Default")
      (node (ref "D205") (pin "1") (pinfunction "A_1") (pintype "passive"))
      (node (ref "S205_1") (pin "1") (pinfunction "1_1") (pintype "passive"))
    )
    (net (code "26") (name "Net-(D206-A)") (class "Default")
      (node (ref "D206") (pin "1") (pinfunction "A_1") (pintype "passive"))
      (node (ref "S206") (pin "1") (pinfunction "1_1") (pintype "passive"))
    )
    (net (code "27") (name "Net-(D207-A)") (class "Default")
      (node (ref "D207") (pin "1") (pinfunction "A_1") (pintype "passive"))
      (node (ref "S207") (pin "1") (pinfunction "1_1") (pintype "passive"))
    )
    (net (code "28") (name "Net-(D208-A)") (class "Default")
      (node (ref "D208") (pin "1") (pinfunction "A_1") (pintype "passive"))
      (node (ref "S208") (pin "1") (pinfunction "1_1") (pintype "passive"))
    )
    (net (code "29") (name "Net-(D209-A)") (class "Default")
      (node (ref "D209") (pin "1") (pinfunction "A_1") (pintype "passive"))
      (node (ref "S209_1") (pin "1") (pinfunction "1_1") (pintype "passive"))
    )
    (net (code "30") (name "Net-(D210-A)") (class "Default")
      (node (ref "D210") (pin "1") (pinfunction "A_1") (pintype "passive"))
      (node (ref "S210") (pin "1") (pinfunction "1_1") (pintype "passive"))
    )
    (net (code "31") (name "Net-(D211-A)") (class "Default")
      (node (ref "D211") (pin "1") (pinfunction "A_1") (pintype "passive"))
      (node (ref "S211") (pin "1") (pinfunction "1_1") (pintype "passive"))
    )
    (net (code "32") (name "Net-(D212-A)") (class "Default")
      (node (ref "D212") (pin "1") (pinfunction "A_1") (pintype "passive"))
      (node (ref "S212") (pin "1") (pinfunction "1_1") (pintype "passive"))
    )
    (net (code "33") (name "Net-(D213-A)") (class "Default")
      (node (ref "D213") (pin "1") (pinfunction "A_1") (pintype "passive"))
      (node (ref "S213") (pin "1") (pinfunction "1_1") (pintype "passive"))
    )
    (net (code "34") (name "Net-(D214-A)") (class "Default")
      (node (ref "D214") (pin "1") (pinfunction "A_1") (pintype "passive"))
      (node (ref "S214") (pin "1") (pinfunction "1_1") (pintype "passive"))
    )
    (net (code "35") (name "Net-(D215-A)") (class "Default")
      (node (ref "D215") (pin "1") (pinfunction "A_1") (pintype "passive"))
      (node (ref "S215") (pin "1") (pinfunction "1_1") (pintype "passive"))
    )
    (net (code "36") (name "Net-(D216-A)") (class "Default")
      (node (ref "D216") (pin "1") (pinfunction "A_1") (pintype "passive"))
      (node (ref "S216") (pin "1") (pinfunction "1_1") (pintype "passive"))
    )
    (net (code "37") (name "Net-(D217-A)") (class "Default")
      (node (ref "D217") (pin "1") (pinfunction "A_1") (pintype "passive"))
      (node (ref "S217") (pin "1") (pinfunction "1_1") (pintype "passive"))
    )
    (net (code "38") (name "Net-(D218-A)") (class "Default")
      (node (ref "D218") (pin "1") (pinfunction "A_1") (pintype "passive"))
      (node (ref "S218") (pin "1") (pinfunction "1_1") (pintype "passive"))
    )
    (net (code "39") (name "Net-(D219-A)") (class "Default")
      (node (ref "D219") (pin "1") (pinfunction "A_1") (pintype "passive"))
      (node (ref "S219") (pin "1") (pinfunction "1_1") (pintype "passive"))
    )
    (net (code "40") (name "Net-(D220-A)") (class "Default")
      (node (ref "D220") (pin "1") (pinfunction "A_1") (pintype "passive"))
      (node (ref "S220") (pin "1") (pinfunction "1_1") (pintype "passive"))
    )
    (net (code "41") (name "Net-(D221-A)") (class "Default")
      (node (ref "D221") (pin "1") (pinfunction "A_1") (pintype "passive"))
      (node (ref "S221") (pin "1") (pinfunction "1_1") (pintype "passive"))
    )
    (net (code "42") (name "Net-(D222-A)") (class "Default")
      (node (ref "D222") (pin "1") (pinfunction "A_1") (pintype "passive"))
      (node (ref "S222") (pin "1") (pinfunction "1_1") (pintype "passive"))
    )
    (net (code "43") (name "Net-(D223-A)") (class "Default")
      (node (ref "D223") (pin "1") (pinfunction "A_1") (pintype "passive"))
      (node (ref "S223") (pin "1") (pinfunction "1_1") (pintype "passive"))
    )
    (net (code "44") (name "Net-(D224-A)") (class "Default")
      (node (ref "D224") (pin "1") (pinfunction "A_1") (pintype "passive"))
      (node (ref "S224") (pin "1") (pinfunction "1_1") (pintype "passive"))
    )
    (net (code "45") (name "Net-(D225-A)") (class "Default")
      (node (ref "D225") (pin "1") (pinfunction "A_1") (pintype "passive"))
      (node (ref "S225") (pin "1") (pinfunction "1_1") (pintype "passive"))
    )
    (net (code "46") (name "Net-(D226-A)") (class "Default")
      (node (ref "D226") (pin "1") (pinfunction "A_1") (pintype "passive"))
      (node (ref "S226") (pin "1") (pinfunction "1_1") (pintype "passive"))
    )
    (net (code "47") (name "Net-(D227-A)") (class "Default")
      (node (ref "D227") (pin "1") (pinfunction "A_1") (pintype "passive"))
      (node (ref "S227") (pin "1") (pinfunction "1_1") (pintype "passive"))
    )
    (net (code "48") (name "Net-(D228-A)") (class "Default")
      (node (ref "D228") (pin "1") (pinfunction "A_1") (pintype "passive"))
      (node (ref "S228") (pin "1") (pinfunction "1_1") (pintype "passive"))
    )
    (net (code "49") (name "Net-(D229-A)") (class "Default")
      (node (ref "D229") (pin "1") (pinfunction "A_1") (pintype "passive"))
      (node (ref "S229") (pin "1") (pinfunction "1_1") (pintype "passive"))
    )
    (net (code "50") (name "Net-(D230-A)") (class "Default")
      (node (ref "D230") (pin "1") (pinfunction "A_1") (pintype "passive"))
      (node (ref "S230") (pin "1") (pinfunction "1_1") (pintype "passive"))
    )
    (net (code "51") (name "Net-(D231-A)") (class "Default")
      (node (ref "D231") (pin "1") (pinfunction "A_1") (pintype "passive"))
      (node (ref "S231") (pin "1") (pinfunction "1_1") (pintype "passive"))
    )
    (net (code "52") (name "Net-(D232-A)") (class "Default")
      (node (ref "D232") (pin "1") (pinfunction "A_1") (pintype "passive"))
      (node (ref "S232") (pin "1") (pinfunction "1_1") (pintype "passive"))
    )
    (net (code "53") (name "Net-(D233-A)") (class "Default")
      (node (ref "D233") (pin "1") (pinfunction "A_1") (pintype "passive"))
      (node (ref "S233") (pin "1") (pinfunction "1_1") (pintype "passive"))
    )
    (net (code "54") (name "Net-(D234-A)") (class "Default")
      (node (ref "D234") (pin "1") (pinfunction "A_1") (pintype "passive"))
      (node (ref "S234") (pin "1") (pinfunction "1_1") (pintype "passive"))
      (node (ref "S234_1") (pin "1") (pinfunction "1_1") (pintype "passive"))
    )
    (net (code "55") (name "Net-(D235-A)") (class "Default")
      (node (ref "D235") (pin "1") (pinfunction "A_1") (pintype "passive"))
      (node (ref "S235") (pin "1") (pinfunction "1_1") (pintype "passive"))
    )
    (net (code "56") (name "Net-(D236-A)") (class "Default")
      (node (ref "D236") (pin "1") (pinfunction "A_1") (pintype "passive"))
      (node (ref "S236") (pin "1") (pinfunction "1_1") (pintype "passive"))
    )
    (net (code "57") (name "Net-(D237-A)") (class "Default")
      (node (ref "D237") (pin "1") (pinfunction "A_1") (pintype "passive"))
      (node (ref "S237") (pin "1") (pinfunction "1_1") (pintype "passive"))
    )
    (net (code "58") (name "Net-(D238-A)") (class "Default")
      (node (ref "D238") (pin "1") (pinfunction "A_1") (pintype "passive"))
      (node (ref "S238") (pin "1") (pinfunction "1_1") (pintype "passive"))
    )
    (net (code "59") (name "Net-(D239-A)") (class "Default")
      (node (ref "D239") (pin "1") (pinfunction "A_1") (pintype "passive"))
      (node (ref "S239") (pin "1") (pinfunction "1_1") (pintype "passive"))
    )
    (net (code "60") (name "Net-(D240-A)") (class "Default")
      (node (ref "D240") (pin "1") (pinfunction "A_1") (pintype "passive"))
      (node (ref "S240") (pin "1") (pinfunction "1_1") (pintype "passive"))
    )
    (net (code "61") (name "Net-(D241-A)") (class "Default")
      (node (ref "D241") (pin "1") (pinfunction "A_1") (pintype "passive"))
      (node (ref "S241") (pin "1") (pinfunction "1_1") (pintype "passive"))
    )
    (net (code "62") (name "Net-(D242-A)") (class "Default")
      (node (ref "D242") (pin "1") (pinfunction "A_1") (pintype "passive"))
      (node (ref "S242") (pin "1") (pinfunction "1_1") (pintype "passive"))
    )
    (net (code "63") (name "Net-(D243-A)") (class "Default")
      (node (ref "D243") (pin "1") (pinfunction "A_1") (pintype "passive"))
      (node (ref "S243") (pin "1") (pinfunction "1_1") (pintype "passive"))
    )
    (net (code "64") (name "Net-(D244-A)") (class "Default")
      (node (ref "D244") (pin "1") (pinfunction "A_1") (pintype "passive"))
      (node (ref "S244") (pin "1") (pinfunction "1_1") (pintype "passive"))
    )
    (net (code "65") (name "Net-(D245-A)") (class "Default")
      (node (ref "D245") (pin "1") (pinfunction "A_1") (pintype "passive"))
      (node (ref "S245") (pin "1") (pinfunction "1_1") (pintype "passive"))
    )
    (net (code "66") (name "Net-(D246-A)") (class "Default")
      (node (ref "D246") (pin "1") (pinfunction "A_1") (pintype "passive"))
      (node (ref "S246") (pin "1") (pinfunction "1_1") (pintype "passive"))
    )
    (net (code "67") (name "Net-(D247-A)") (class "Default")
      (node (ref "D247") (pin "1") (pinfunction "A_1") (pintype "passive"))
      (node (ref "S247") (pin "1") (pinfunction "1_1") (pintype "passive"))
      (node (ref "S247_1") (pin "1") (pinfunction "1_1") (pintype "passive"))
    )
    (net (code "68") (name "Net-(D248-A)") (class "Default")
      (node (ref "D248") (pin "1") (pinfunction "A_1") (pintype "passive"))
      (node (ref "S248") (pin "1") (pinfunction "1_1") (pintype "passive"))
    )
    (net (code "69") (name "Net-(D249-A)") (class "Default")
      (node (ref "D249") (pin "1") (pinfunction "A_1") (pintype "passive"))
      (node (ref "S249") (pin "1") (pinfunction "1_1") (pintype "passive"))
    )
    (net (code "70") (name "Net-(D250-A)") (class "Default")
      (node (ref "D250") (pin "1") (pinfunction "A_1") (pintype "passive"))
      (node (ref "S250") (pin "1") (pinfunction "1_1") (pintype "passive"))
    )
    (net (code "71") (name "Net-(D251-A)") (class "Default")
      (node (ref "D251") (pin "1") (pinfunction "A_1") (pintype "passive"))
      (node (ref "S251") (pin "1") (pinfunction "1_1") (pintype "passive"))
    )
    (net (code "72") (name "Net-(D252-A)") (class "Default")
      (node (ref "D252") (pin "1") (pinfunction "A_1") (pintype "passive"))
      (node (ref "S252") (pin "1") (pinfunction "1_1") (pintype "passive"))
    )
    (net (code "73") (name "Net-(D253-A)") (class "Default")
      (node (ref "D253") (pin "1") (pinfunction "A_1") (pintype "passive"))
      (node (ref "S253") (pin "1") (pinfunction "1_1") (pintype "passive"))
    )
    (net (code "74") (name "Net-(D254-A)") (class "Default")
      (node (ref "D254") (pin "1") (pinfunction "A_1") (pintype "passive"))
      (node (ref "S254") (pin "1") (pinfunction "1_1") (pintype "passive"))
    )
    (net (code "75") (name "Net-(D255-A)") (class "Default")
      (node (ref "D255") (pin "1") (pinfunction "A_1") (pintype "passive"))
      (node (ref "S255") (pin "1") (pinfunction "1_1") (pintype "passive"))
    )
    (net (code "76") (name "Net-(D256-A)") (class "Default")
      (node (ref "D256") (pin "1") (pinfunction "A_1") (pintype "passive"))
      (node (ref "S256") (pin "1") (pinfunction "1_1") (pintype "passive"))
    )
    (net (code "77") (name "Net-(D257-A)") (class "Default")
      (node (ref "D257") (pin "1") (pinfunction "A_1") (pintype "passive"))
      (node (ref "S257") (pin "1") (pinfunction "1_1") (pintype "passive"))
    )
    (net (code "78") (name "Net-(D258-A)") (class "Default")
      (node (ref "D258") (pin "1") (pinfunction "A_1") (pintype "passive"))
      (node (ref "S258") (pin "1") (pinfunction "1_1") (pintype "passive"))
    )
    (net (code "79") (name "Net-(D259-A)") (class "Default")
      (node (ref "D259") (pin "1") (pinfunction "A_1") (pintype "passive"))
      (node (ref "S259") (pin "1") (pinfunction "1_1") (pintype "passive"))
    )
    (net (code "80") (name "Net-(D260-A)") (class "Default")
      (node (ref "D260") (pin "1") (pinfunction "A_1") (pintype "passive"))
      (node (ref "S260") (pin "1") (pinfunction "1_1") (pintype "passive"))
    )
    (net (code "81") (name "Net-(D261-A)") (class "Default")
      (node (ref "D261") (pin "1") (pinfunction "A_1") (pintype "passive"))
      (node (ref "S261") (pin "1") (pinfunction "1_1") (pintype "passive"))
    )
    (net (code "82") (name "Net-(D262-A)") (class "Default")
      (node (ref "D262") (pin "1") (pinfunction "A_1") (pintype "passive"))
      (node (ref "S262") (pin "1") (pinfunction "1_1") (pintype "passive"))
    )
    (net (code "83") (name "Net-(D263-A)") (class "Default")
      (node (ref "D263") (pin "1") (pinfunction "A_1") (pintype "passive"))
      (node (ref "S263") (pin "1") (pinfunction "1_1") (pintype "passive"))
    )
    (net (code "84") (name "Net-(D264-A)") (class "Default")
      (node (ref "D264") (pin "1") (pinfunction "A_1") (pintype "passive"))
      (node (ref "S264") (pin "1") (pinfunction "1_1") (pintype "passive"))
      (node (ref "S264_1") (pin "1") (pinfunction "1_1") (pintype "passive"))
    )
    (net (code "85") (name "Net-(D265-A)") (class "Default")
      (node (ref "D265") (pin "1") (pinfunction "A_1") (pintype "passive"))
      (node (ref "S265") (pin "1") (pinfunction "1_1") (pintype "passive"))
      (node (ref "S265_1") (pin "1") (pinfunction "1_1") (pintype "passive"))
      (node (ref "S265_2") (pin "1") (pinfunction "1_1") (pintype "passive"))
      (node (ref "S265_3") (pin "1") (pinfunction "1_1") (pintype "passive"))
    )
    (net (code "86") (name "Net-(D266-A)") (class "Default")
      (node (ref "D266") (pin "1") (pinfunction "A_1") (pintype "passive"))
      (node (ref "S266") (pin "1") (pinfunction "1_1") (pintype "passive"))
    )
    (net (code "87") (name "Net-(D267-A)") (class "Default")
      (node (ref "D267") (pin "1") (pinfunction "A_1") (pintype "passive"))
      (node (ref "S267") (pin "1") (pinfunction "1_1") (pintype "passive"))
    )
    (net (code "88") (name "Net-(D268-A)") (class "Default")
      (node (ref "D268") (pin "1") (pinfunction "A_1") (pintype "passive"))
      (node (ref "S268") (pin "1") (pinfunction "1_1") (pintype "passive"))
    )
    (net (code "89") (name "Net-(D269-A)") (class "Default")
      (node (ref "D269") (pin "1") (pinfunction "A_1") (pintype "passive"))
      (node (ref "S269") (pin "1") (pinfunction "1_1") (pintype "passive"))
    )
    (net (code "90") (name "Net-(D270-A)") (class "Default")
      (node (ref "D270") (pin "1") (pinfunction "A_1") (pintype "passive"))
      (node (ref "S270") (pin "1") (pinfunction "1_1") (pintype "passive"))
    )
    (net (code "91") (name "Net-(D271-A)") (class "Default")
      (node (ref "D271") (pin "1") (pinfunction "A_1") (pintype "passive"))
      (node (ref "S271") (pin "1") (pinfunction "1_1") (pintype "passive"))
    )
    (net (code "92") (name "Net-(D272-A)") (class "Default")
      (node (ref "D272") (pin "1") (pinfunction "A_1") (pintype "passive"))
      (node (ref "S272") (pin "1") (pinfunction "1_1") (pintype "passive"))
    )
    (net (code "93") (name "Net-(D273-A)") (class "Default")
      (node (ref "D273") (pin "1") (pinfunction "A_1") (pintype "passive"))
      (node (ref "S273") (pin "1") (pinfunction "1_1") (pintype "passive"))
    )
    (net (code "94") (name "Net-(D274-A)") (class "Default")
      (node (ref "D274") (pin "1") (pinfunction "A_1") (pintype "passive"))
      (node (ref "S274") (pin "1") (pinfunction "1_1") (pintype "passive"))
    )
    (net (code "95") (name "Net-(D275-A)") (class "Default")
      (node (ref "D275") (pin "1") (pinfunction "A_1") (pintype "passive"))
      (node (ref "S275") (pin "1") (pinfunction "1_1") (pintype "passive"))
    )
    (net (code "96") (name "Net-(D276-A)") (class "Default")
      (node (ref "D276") (pin "1") (pinfunction "A_1") (pintype "passive"))
      (node (ref "S276") (pin "1") (pinfunction "1_1") (pintype "passive"))
    )
    (net (code "97") (name "Net-(D277-A)") (class "Default")
      (node (ref "D277") (pin "1") (pinfunction "A_1") (pintype "passive"))
      (node (ref "S277") (pin "1") (pinfunction "1_1") (pintype "passive"))
      (node (ref "S277_1") (pin "1") (pinfunction "1_1") (pintype "passive"))
      (node (ref "S277_2") (pin "1") (pinfunction "1_1") (pintype "passive"))
    )
    (net (code "98") (name "Net-(D278-A)") (class "Default")
      (node (ref "D278") (pin "1") (pinfunction "A_1") (pintype "passive"))
      (node (ref "S278") (pin "1") (pinfunction "1_1") (pintype "passive"))
    )
    (net (code "99") (name "Net-(D279-A)") (class "Default")
      (node (ref "D279") (pin "1") (pinfunction "A_1") (pintype "passive"))
      (node (ref "S279") (pin "1") (pinfunction "1_1") (pintype "passive"))
    )
    (net (code "100") (name "Net-(D280-A)") (class "Default")
      (node (ref "D280") (pin "1") (pinfunction "A_1") (pintype "passive"))
      (node (ref "S280") (pin "2") (pinfunction "2_2") (pintype "passive"))
    )
    (net (code "101") (name "Net-(D281-A)") (class "Default")
      (node (ref "D281") (pin "1") (pinfunction "A_1") (pintype "passive"))
      (node (ref "S281") (pin "2") (pinfunction "2_2") (pintype "passive"))
    )
    (net (code "102") (name "Net-(D282-A)") (class "Default")
      (node (ref "D282") (pin "1") (pinfunction "A_1") (pintype "passive"))
      (node (ref "S282") (pin "2") (pinfunction "2_2") (pintype "passive"))
    )
    (net (code "103") (name "Net-(D283-A)") (class "Default")
      (node (ref "D283") (pin "1") (pinfunction "A_1") (pintype "passive"))
      (node (ref "S283") (pin "1") (pinfunction "1_1") (pintype "passive"))
    )
    (net (code "104") (name "Net-(D284-A)") (class "Default")
      (node (ref "D284") (pin "1") (pinfunction "A_1") (pintype "passive"))
      (node (ref "S284") (pin "1") (pinfunction "1_1") (pintype "passive"))
    )
    (net (code "105") (name "Net-(D285-A)") (class "Default")
      (node (ref "D285") (pin "1") (pinfunction "A_1") (pintype "passive"))
      (node (ref "S285") (pin "1") (pinfunction "1_1") (pintype "passive"))
    )
    (net (code "106") (name "Net-(D286-A)") (class "Default")
      (node (ref "D286") (pin "1") (pinfunction "A_1") (pintype "passive"))
      (node (ref "S286") (pin "1") (pinfunction "1_1") (pintype "passive"))
    )
    (net (code "107") (name "Net-(D287-A)") (class "Default")
      (node (ref "D287") (pin "1") (pinfunction "A_1") (pintype "passive"))
      (node (ref "S287") (pin "1") (pinfunction "1_1") (pintype "passive"))
    )
    (net (code "108") (name "Net-(D288-A)") (class "Default")
      (node (ref "D288") (pin "1") (pinfunction "A_1") (pintype "passive"))
      (node (ref "S288") (pin "1") (pinfunction "1_1") (pintype "passive"))
    )
    (net (code "109") (name "Net-(D289-A)") (class "Default")
      (node (ref "D289") (pin "1") (pinfunction "A_1") (pintype "passive"))
      (node (ref "S289") (pin "1") (pinfunction "1_1") (pintype "passive"))
    )
    (net (code "110") (name "Net-(D296-A)") (class "Default")
      (node (ref "D296") (pin "1") (pinfunction "A_1") (pintype "passive"))
      (node (ref "S296") (pin "1") (pinfunction "1_1") (pintype "passive"))
      (node (ref "S296_1") (pin "1") (pinfunction "1_1") (pintype "passive"))
      (node (ref "S296_2") (pin "1") (pinfunction "1_1") (pintype "passive"))
    )
  )
)
